# 1-Schematic_EMWAVER_DIY_V1.net
KiCad netlist of a schematic drawn in EasyEDA
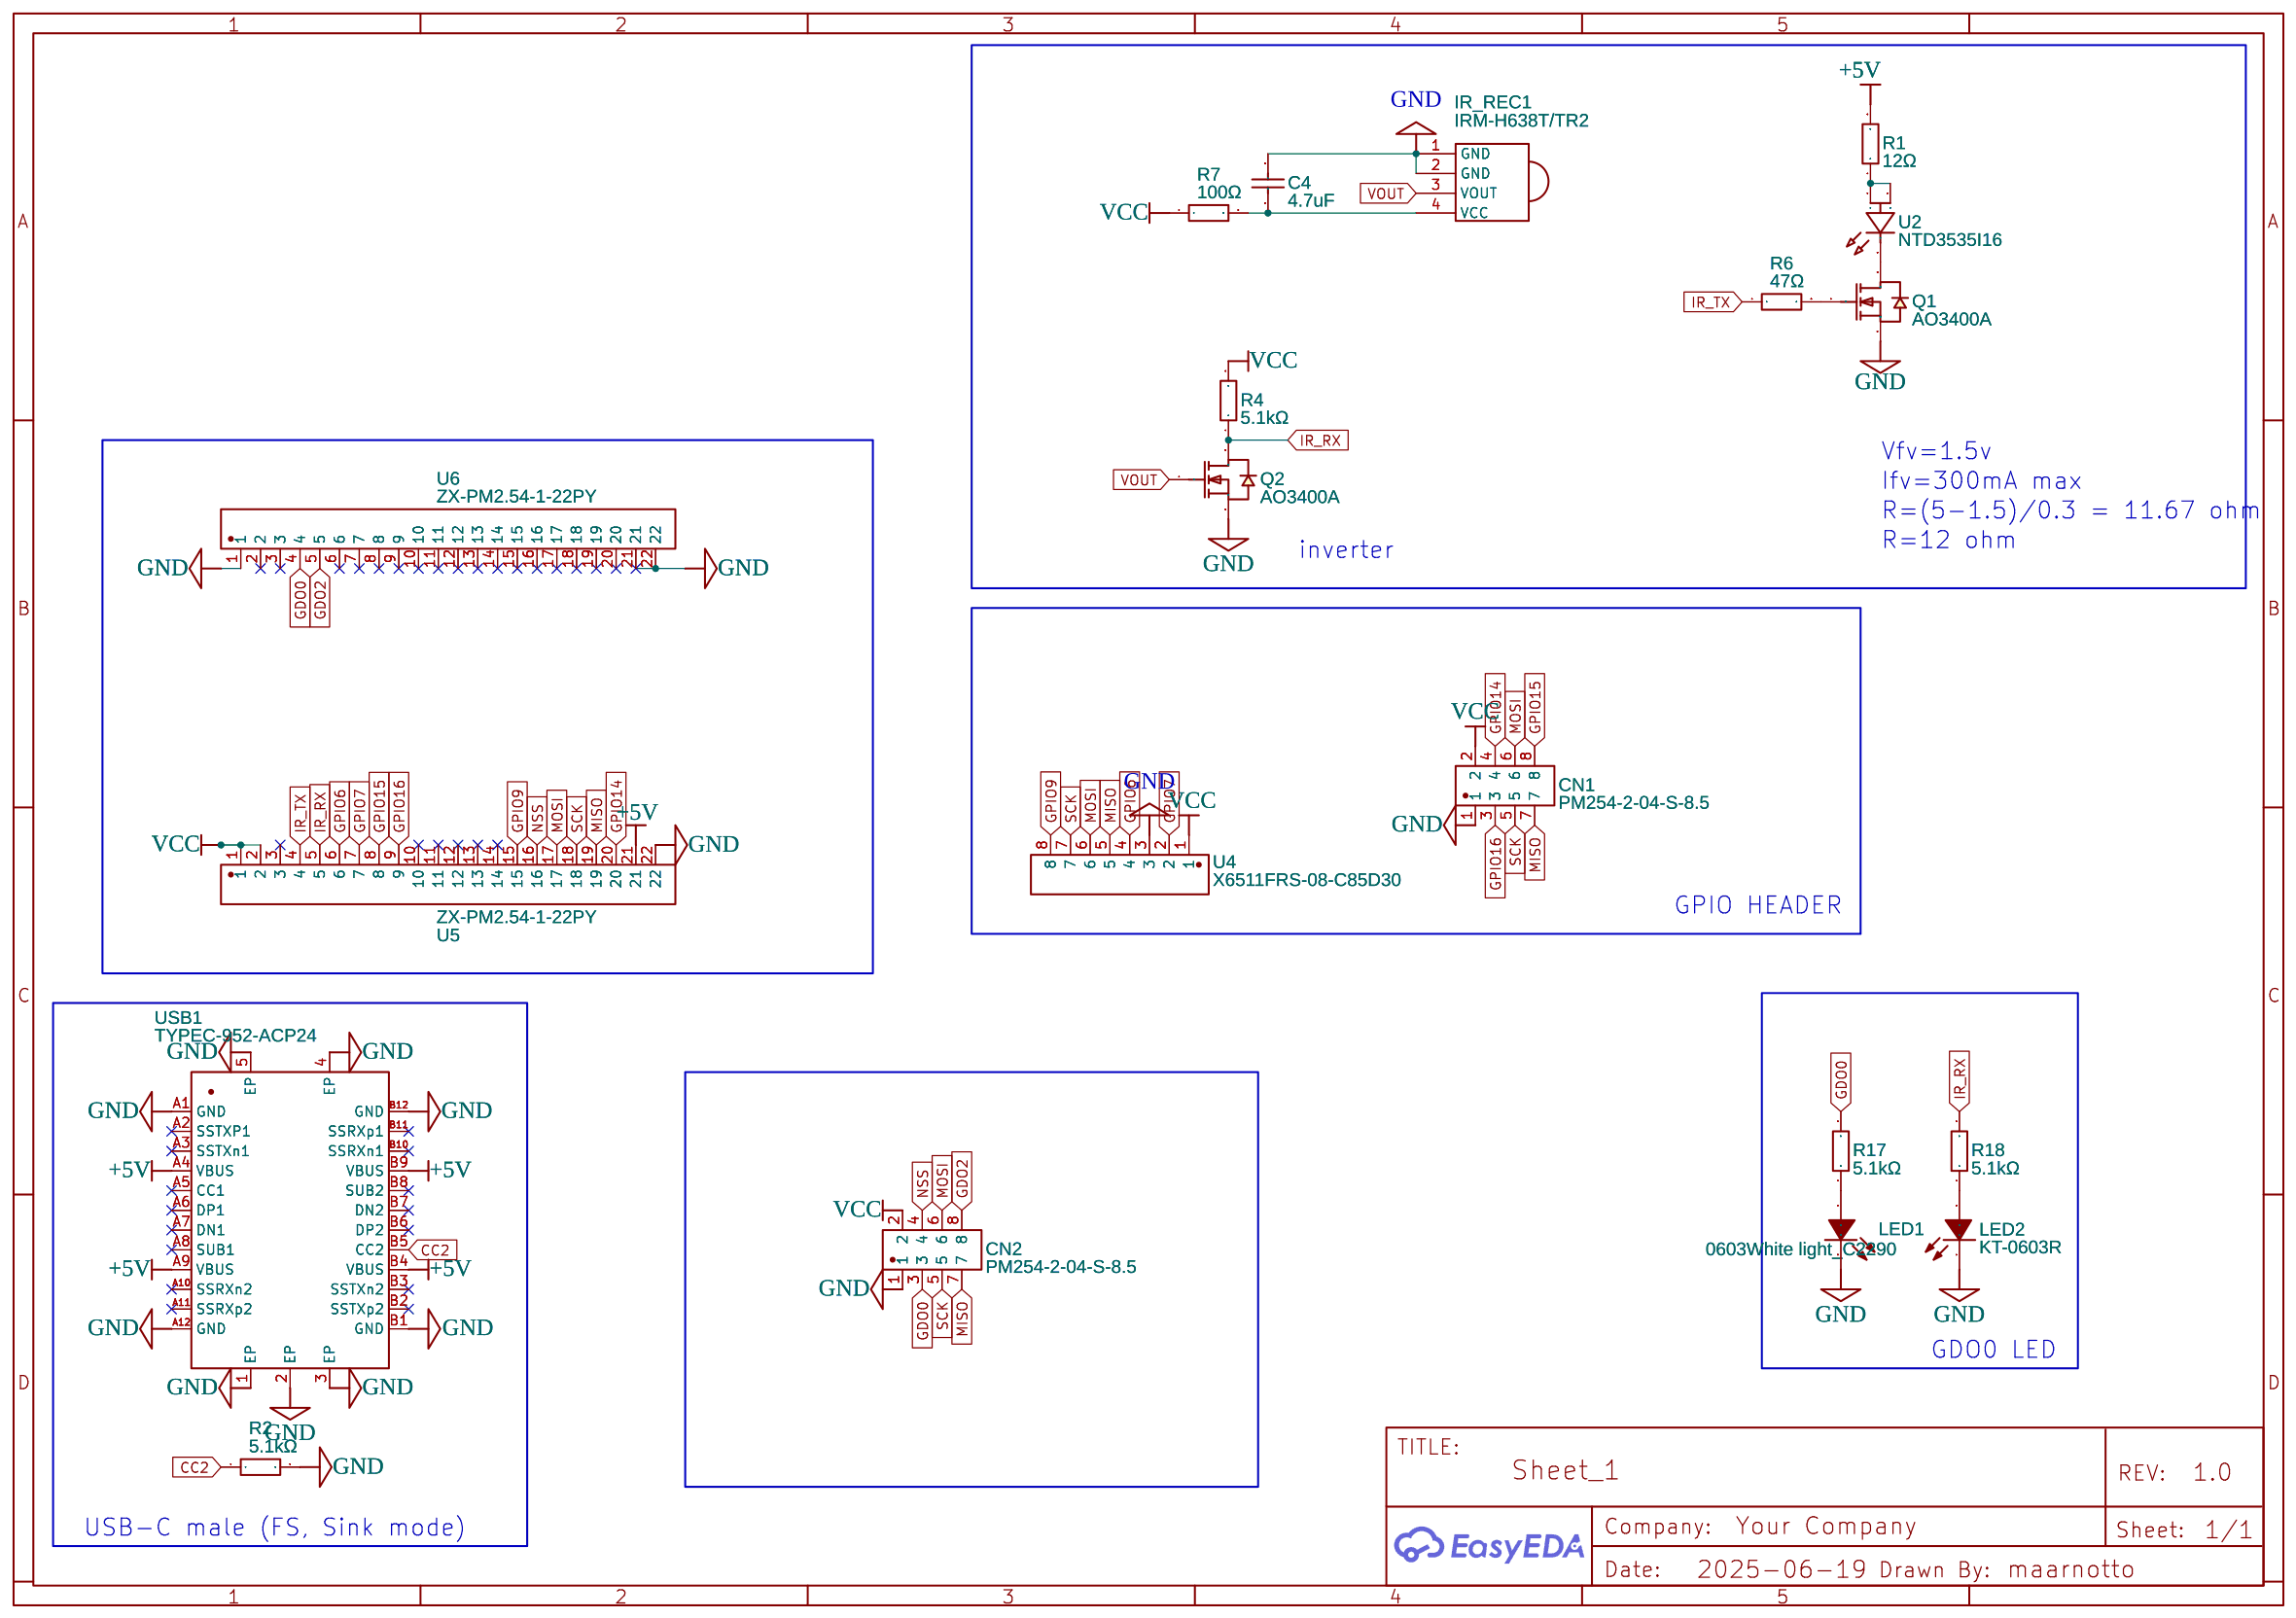
[diagram p0: schematic sheet]

(export (version "E")
  (design (tool "Eeschema 10.0.6"))
  (components
    (comp (ref "C4")
      (value "4.7uF")
      (fields
        (field (name "Manufacturer Part") "CL10A475KO8NNNC")
        (field (name "Manufacturer") "SAMSUNG(三星)")
      )
      (libsource (lib "") (part "CL10A475KO8NNNC"))
    )
    (comp (ref "CN1")
      (value "PM254-2-04-S-8.5")
      (fields (field (name "Manufacturer") "HCTL(华灿天禄)"))
      (libsource (lib "") (part "PM254-2-04-S-8.5"))
    )
    (comp (ref "CN2")
      (value "PM254-2-04-S-8.5")
      (fields (field (name "Manufacturer") "HCTL(华灿天禄)"))
      (libsource (lib "") (part "PM254-2-04-S-8.5"))
    )
    (comp (ref "IR_REC1")
      (value "IRM-H638T/TR2")
      (fields (field (name "Manufacturer") "EVERLIGHT(亿光)"))
      (libsource (lib "") (part "IRM-H638T/TR2"))
    )
    (comp (ref "LED1")
      (value "0603White light_C2290")
      (fields (field (name "Manufacturer Part") "KT-0603W") (field (name "Manufacturer") "KENTO"))
      (libsource (lib "") (part "0603White light_C2290"))
    )
    (comp (ref "LED2")
      (value "KT-0603R")
      (fields (field (name "Manufacturer") "KENTO"))
      (libsource (lib "") (part "KT-0603R"))
    )
    (comp (ref "Q1")
      (value "AO3400A")
      (fields (field (name "Manufacturer") "AOS"))
      (libsource (lib "") (part "AO3400A"))
    )
    (comp (ref "Q2")
      (value "AO3400A")
      (fields (field (name "Manufacturer") "AOS"))
      (libsource (lib "") (part "AO3400A"))
    )
    (comp (ref "R1")
      (value "12Ω")
      (fields
        (field (name "Manufacturer Part") "25121WJ0120T4E")
        (field (name "Manufacturer") "UNI-ROYAL(厚声)")
      )
      (libsource (lib "") (part "25121WJ0120T4E"))
    )
    (comp (ref "R2")
      (value "5.1kΩ")
      (fields
        (field (name "Manufacturer Part") "0603WAF5101T5E")
        (field (name "Manufacturer") "UNI-ROYAL(厚声)")
      )
      (libsource (lib "") (part "0603WAF5101T5E_1"))
    )
    (comp (ref "R4")
      (value "5.1kΩ")
      (fields
        (field (name "Manufacturer Part") "0603WAF5101T5E")
        (field (name "Manufacturer") "UNI-ROYAL(厚声)")
      )
      (libsource (lib "") (part "0603WAF5101T5E"))
    )
    (comp (ref "R6")
      (value "47Ω")
      (fields
        (field (name "Manufacturer Part") "0805W8F470JT5E")
        (field (name "Manufacturer") "UNI-ROYAL(厚声)")
      )
      (libsource (lib "") (part "0805W8F470JT5E"))
    )
    (comp (ref "R7")
      (value "100Ω")
      (fields
        (field (name "Manufacturer Part") "0805W8F1000T5E")
        (field (name "Manufacturer") "UNI-ROYAL(厚声)")
      )
      (libsource (lib "") (part "0805W8F1000T5E"))
    )
    (comp (ref "R17")
      (value "5.1kΩ")
      (fields
        (field (name "Manufacturer Part") "0603WAF5101T5E")
        (field (name "Manufacturer") "UNI-ROYAL(厚声)")
      )
      (libsource (lib "") (part "0603WAF5101T5E"))
    )
    (comp (ref "R18")
      (value "5.1kΩ")
      (fields
        (field (name "Manufacturer Part") "0603WAF5101T5E")
        (field (name "Manufacturer") "UNI-ROYAL(厚声)")
      )
      (libsource (lib "") (part "0603WAF5101T5E"))
    )
    (comp (ref "U2")
      (value "NTD3535I16")
      (fields (field (name "Manufacturer") "国星光电"))
      (libsource (lib "") (part "NTD3535I16"))
    )
    (comp (ref "U4")
      (value "X6511FRS-08-C85D30")
      (fields (field (name "Manufacturer") "XKB Connectivity(中国星坤)"))
      (libsource (lib "") (part "X6511FRS-08-C85D30"))
    )
    (comp (ref "U5")
      (value "ZX-PM2.54-1-22PY")
      (fields (field (name "Manufacturer") "Megastar(兆星)"))
      (libsource (lib "") (part "ZX-PM2.54-1-22PY_1"))
    )
    (comp (ref "U6")
      (value "ZX-PM2.54-1-22PY")
      (fields (field (name "Manufacturer") "Megastar(兆星)"))
      (libsource (lib "") (part "ZX-PM2.54-1-22PY"))
    )
    (comp (ref "USB1")
      (value "TYPEC-952-ACP24")
      (fields (field (name "Manufacturer") "XUNPU(讯普)"))
      (libsource (lib "") (part "TYPEC-952-ACP24"))
    )
  )
  (nets
    (net (code "1") (name "+5V") (class "Default")
      (node (ref "R1") (pin "2") (pinfunction "2_2") (pintype "input"))
      (node (ref "U5") (pin "21") (pinfunction "21_21") (pintype "unspecified"))
      (node (ref "USB1") (pin "A4") (pinfunction "VBUS_A4") (pintype "unspecified"))
      (node (ref "USB1") (pin "A9") (pinfunction "VBUS_A9") (pintype "unspecified"))
      (node (ref "USB1") (pin "B4") (pinfunction "VBUS_B4") (pintype "unspecified"))
      (node (ref "USB1") (pin "B9") (pinfunction "VBUS_B9") (pintype "unspecified"))
    )
    (net (code "2") (name "CC2") (class "Default")
      (node (ref "R2") (pin "1") (pinfunction "1_1") (pintype "input"))
      (node (ref "USB1") (pin "B5") (pinfunction "CC2_B5") (pintype "unspecified"))
    )
    (net (code "3") (name "GDO0") (class "Default")
      (node (ref "CN2") (pin "3") (pinfunction "3_3") (pintype "unspecified"))
      (node (ref "R17") (pin "2") (pinfunction "2_2") (pintype "input"))
      (node (ref "U6") (pin "4") (pinfunction "4_4") (pintype "unspecified"))
    )
    (net (code "4") (name "GDO2") (class "Default")
      (node (ref "CN2") (pin "8") (pinfunction "8_8") (pintype "unspecified"))
      (node (ref "U6") (pin "5") (pinfunction "5_5") (pintype "unspecified"))
    )
    (net (code "5") (name "GND") (class "Default")
      (node (ref "C4") (pin "2") (pinfunction "2_2") (pintype "input"))
      (node (ref "CN1") (pin "1") (pinfunction "1_1") (pintype "unspecified"))
      (node (ref "CN2") (pin "1") (pinfunction "1_1") (pintype "unspecified"))
      (node (ref "IR_REC1") (pin "1") (pinfunction "GND_1") (pintype "input"))
      (node (ref "IR_REC1") (pin "2") (pinfunction "GND_2") (pintype "input"))
      (node (ref "LED1") (pin "2") (pinfunction "K_2") (pintype "unspecified"))
      (node (ref "LED2") (pin "1") (pinfunction "K_1") (pintype "unspecified"))
      (node (ref "Q1") (pin "2") (pinfunction "S_2") (pintype "unspecified"))
      (node (ref "Q2") (pin "2") (pinfunction "S_2") (pintype "unspecified"))
      (node (ref "R2") (pin "2") (pinfunction "2_2") (pintype "input"))
      (node (ref "U4") (pin "3") (pinfunction "3_3") (pintype "unspecified"))
      (node (ref "U5") (pin "22") (pinfunction "22_22") (pintype "unspecified"))
      (node (ref "U6") (pin "1") (pinfunction "1_1") (pintype "unspecified"))
      (node (ref "U6") (pin "21") (pinfunction "21_21") (pintype "unspecified"))
      (node (ref "U6") (pin "22") (pinfunction "22_22") (pintype "unspecified"))
      (node (ref "USB1") (pin "1") (pinfunction "EP_1") (pintype "unspecified"))
      (node (ref "USB1") (pin "2") (pinfunction "EP_2") (pintype "unspecified"))
      (node (ref "USB1") (pin "3") (pinfunction "EP_3") (pintype "unspecified"))
      (node (ref "USB1") (pin "4") (pinfunction "EP_4") (pintype "unspecified"))
      (node (ref "USB1") (pin "5") (pinfunction "EP_5") (pintype "unspecified"))
      (node (ref "USB1") (pin "A1") (pinfunction "GND_A1") (pintype "unspecified"))
      (node (ref "USB1") (pin "A12") (pinfunction "GND_A12") (pintype "unspecified"))
      (node (ref "USB1") (pin "B1") (pinfunction "GND_B1") (pintype "unspecified"))
      (node (ref "USB1") (pin "B12") (pinfunction "GND_B12") (pintype "unspecified"))
    )
    (net (code "6") (name "GPIO6") (class "Default")
      (node (ref "U4") (pin "4") (pinfunction "4_4") (pintype "unspecified"))
      (node (ref "U5") (pin "6") (pinfunction "6_6") (pintype "unspecified"))
    )
    (net (code "7") (name "GPIO7") (class "Default")
      (node (ref "U4") (pin "2") (pinfunction "2_2") (pintype "unspecified"))
      (node (ref "U5") (pin "7") (pinfunction "7_7") (pintype "unspecified"))
    )
    (net (code "8") (name "GPIO9") (class "Default")
      (node (ref "U4") (pin "8") (pinfunction "8_8") (pintype "unspecified"))
      (node (ref "U5") (pin "15") (pinfunction "15_15") (pintype "unspecified"))
    )
    (net (code "9") (name "GPIO14") (class "Default")
      (node (ref "CN1") (pin "4") (pinfunction "4_4") (pintype "unspecified"))
      (node (ref "U5") (pin "20") (pinfunction "20_20") (pintype "unspecified"))
    )
    (net (code "10") (name "GPIO15") (class "Default")
      (node (ref "CN1") (pin "8") (pinfunction "8_8") (pintype "unspecified"))
      (node (ref "U5") (pin "8") (pinfunction "8_8") (pintype "unspecified"))
    )
    (net (code "11") (name "GPIO16") (class "Default")
      (node (ref "CN1") (pin "3") (pinfunction "3_3") (pintype "unspecified"))
      (node (ref "U5") (pin "9") (pinfunction "9_9") (pintype "unspecified"))
    )
    (net (code "12") (name "IR_RX") (class "Default")
      (node (ref "Q2") (pin "3") (pinfunction "D_3") (pintype "unspecified"))
      (node (ref "R18") (pin "2") (pinfunction "2_2") (pintype "input"))
      (node (ref "R4") (pin "1") (pinfunction "1_1") (pintype "input"))
      (node (ref "U5") (pin "5") (pinfunction "5_5") (pintype "unspecified"))
    )
    (net (code "13") (name "IR_TX") (class "Default")
      (node (ref "R6") (pin "1") (pinfunction "1_1") (pintype "input"))
      (node (ref "U5") (pin "4") (pinfunction "4_4") (pintype "unspecified"))
    )
    (net (code "14") (name "MISO") (class "Default")
      (node (ref "CN1") (pin "7") (pinfunction "7_7") (pintype "unspecified"))
      (node (ref "CN2") (pin "7") (pinfunction "7_7") (pintype "unspecified"))
      (node (ref "U4") (pin "5") (pinfunction "5_5") (pintype "unspecified"))
      (node (ref "U5") (pin "19") (pinfunction "19_19") (pintype "unspecified"))
    )
    (net (code "15") (name "MOSI") (class "Default")
      (node (ref "CN1") (pin "6") (pinfunction "6_6") (pintype "unspecified"))
      (node (ref "CN2") (pin "6") (pinfunction "6_6") (pintype "unspecified"))
      (node (ref "U4") (pin "6") (pinfunction "6_6") (pintype "unspecified"))
      (node (ref "U5") (pin "17") (pinfunction "17_17") (pintype "unspecified"))
    )
    (net (code "16") (name "NSS") (class "Default")
      (node (ref "CN2") (pin "4") (pinfunction "4_4") (pintype "unspecified"))
      (node (ref "U5") (pin "16") (pinfunction "16_16") (pintype "unspecified"))
    )
    (net (code "17") (name "Net-(IR_REC1-VCC)") (class "Default")
      (node (ref "C4") (pin "1") (pinfunction "1_1") (pintype "input"))
      (node (ref "IR_REC1") (pin "4") (pinfunction "VCC_4") (pintype "input"))
      (node (ref "R7") (pin "2") (pinfunction "2_2") (pintype "input"))
    )
    (net (code "18") (name "Net-(LED1-A)") (class "Default")
      (node (ref "LED1") (pin "1") (pinfunction "A_1") (pintype "unspecified"))
      (node (ref "R17") (pin "1") (pinfunction "1_1") (pintype "input"))
    )
    (net (code "19") (name "Net-(LED2-A)") (class "Default")
      (node (ref "LED2") (pin "2") (pinfunction "A_2") (pintype "unspecified"))
      (node (ref "R18") (pin "1") (pinfunction "1_1") (pintype "input"))
    )
    (net (code "20") (name "Net-(Q1-D)") (class "Default")
      (node (ref "Q1") (pin "3") (pinfunction "D_3") (pintype "unspecified"))
      (node (ref "U2") (pin "3") (pinfunction "K_3") (pintype "unspecified"))
    )
    (net (code "21") (name "Net-(Q1-G)") (class "Default")
      (node (ref "Q1") (pin "1") (pinfunction "G_1") (pintype "unspecified"))
      (node (ref "R6") (pin "2") (pinfunction "2_2") (pintype "input"))
    )
    (net (code "22") (name "Net-(U2-A)") (class "Default")
      (node (ref "R1") (pin "1") (pinfunction "1_1") (pintype "input"))
      (node (ref "U2") (pin "1") (pinfunction "A_1") (pintype "unspecified"))
      (node (ref "U2") (pin "2") (pinfunction "2_2") (pintype "unspecified"))
    )
    (net (code "23") (name "SCK") (class "Default")
      (node (ref "CN1") (pin "5") (pinfunction "5_5") (pintype "unspecified"))
      (node (ref "CN2") (pin "5") (pinfunction "5_5") (pintype "unspecified"))
      (node (ref "U4") (pin "7") (pinfunction "7_7") (pintype "unspecified"))
      (node (ref "U5") (pin "18") (pinfunction "18_18") (pintype "unspecified"))
    )
    (net (code "24") (name "VCC") (class "Default")
      (node (ref "CN1") (pin "2") (pinfunction "2_2") (pintype "unspecified"))
      (node (ref "CN2") (pin "2") (pinfunction "2_2") (pintype "unspecified"))
      (node (ref "R4") (pin "2") (pinfunction "2_2") (pintype "input"))
      (node (ref "R7") (pin "1") (pinfunction "1_1") (pintype "input"))
      (node (ref "U4") (pin "1") (pinfunction "1_1") (pintype "unspecified"))
      (node (ref "U5") (pin "1") (pinfunction "1_1") (pintype "unspecified"))
      (node (ref "U5") (pin "2") (pinfunction "2_2") (pintype "unspecified"))
    )
    (net (code "25") (name "VOUT") (class "Default")
      (node (ref "IR_REC1") (pin "3") (pinfunction "VOUT_3") (pintype "input"))
      (node (ref "Q2") (pin "1") (pinfunction "G_1") (pintype "unspecified"))
    )
    (net (code "26") (name "unconnected-(U5-Pad3)") (class "Default")
      (node (ref "U5") (pin "3") (pinfunction "3_3") (pintype "unspecified+no_connect"))
    )
    (net (code "27") (name "unconnected-(U5-Pad10)") (class "Default")
      (node (ref "U5") (pin "10") (pinfunction "10_10") (pintype "unspecified+no_connect"))
    )
    (net (code "28") (name "unconnected-(U5-Pad11)") (class "Default")
      (node (ref "U5") (pin "11") (pinfunction "11_11") (pintype "unspecified+no_connect"))
    )
    (net (code "29") (name "unconnected-(U5-Pad12)") (class "Default")
      (node (ref "U5") (pin "12") (pinfunction "12_12") (pintype "unspecified+no_connect"))
    )
    (net (code "30") (name "unconnected-(U5-Pad13)") (class "Default")
      (node (ref "U5") (pin "13") (pinfunction "13_13") (pintype "unspecified+no_connect"))
    )
    (net (code "31") (name "unconnected-(U5-Pad14)") (class "Default")
      (node (ref "U5") (pin "14") (pinfunction "14_14") (pintype "unspecified+no_connect"))
    )
    (net (code "32") (name "unconnected-(U6-Pad2)") (class "Default")
      (node (ref "U6") (pin "2") (pinfunction "2_2") (pintype "unspecified+no_connect"))
    )
    (net (code "33") (name "unconnected-(U6-Pad3)") (class "Default")
      (node (ref "U6") (pin "3") (pinfunction "3_3") (pintype "unspecified+no_connect"))
    )
    (net (code "34") (name "unconnected-(U6-Pad6)") (class "Default")
      (node (ref "U6") (pin "6") (pinfunction "6_6") (pintype "unspecified+no_connect"))
    )
    (net (code "35") (name "unconnected-(U6-Pad7)") (class "Default")
      (node (ref "U6") (pin "7") (pinfunction "7_7") (pintype "unspecified+no_connect"))
    )
    (net (code "36") (name "unconnected-(U6-Pad8)") (class "Default")
      (node (ref "U6") (pin "8") (pinfunction "8_8") (pintype "unspecified+no_connect"))
    )
    (net (code "37") (name "unconnected-(U6-Pad9)") (class "Default")
      (node (ref "U6") (pin "9") (pinfunction "9_9") (pintype "unspecified+no_connect"))
    )
    (net (code "38") (name "unconnected-(U6-Pad10)") (class "Default")
      (node (ref "U6") (pin "10") (pinfunction "10_10") (pintype "unspecified+no_connect"))
    )
    (net (code "39") (name "unconnected-(U6-Pad11)") (class "Default")
      (node (ref "U6") (pin "11") (pinfunction "11_11") (pintype "unspecified+no_connect"))
    )
    (net (code "40") (name "unconnected-(U6-Pad12)") (class "Default")
      (node (ref "U6") (pin "12") (pinfunction "12_12") (pintype "unspecified+no_connect"))
    )
    (net (code "41") (name "unconnected-(U6-Pad13)") (class "Default")
      (node (ref "U6") (pin "13") (pinfunction "13_13") (pintype "unspecified+no_connect"))
    )
    (net (code "42") (name "unconnected-(U6-Pad14)") (class "Default")
      (node (ref "U6") (pin "14") (pinfunction "14_14") (pintype "unspecified+no_connect"))
    )
    (net (code "43") (name "unconnected-(U6-Pad15)") (class "Default")
      (node (ref "U6") (pin "15") (pinfunction "15_15") (pintype "unspecified+no_connect"))
    )
    (net (code "44") (name "unconnected-(U6-Pad16)") (class "Default")
      (node (ref "U6") (pin "16") (pinfunction "16_16") (pintype "unspecified+no_connect"))
    )
    (net (code "45") (name "unconnected-(U6-Pad17)") (class "Default")
      (node (ref "U6") (pin "17") (pinfunction "17_17") (pintype "unspecified+no_connect"))
    )
    (net (code "46") (name "unconnected-(U6-Pad18)") (class "Default")
      (node (ref "U6") (pin "18") (pinfunction "18_18") (pintype "unspecified+no_connect"))
    )
    (net (code "47") (name "unconnected-(U6-Pad19)") (class "Default")
      (node (ref "U6") (pin "19") (pinfunction "19_19") (pintype "unspecified+no_connect"))
    )
    (net (code "48") (name "unconnected-(U6-Pad20)") (class "Default")
      (node (ref "U6") (pin "20") (pinfunction "20_20") (pintype "unspecified+no_connect"))
    )
    (net (code "49") (name "unconnected-(USB1-CC1-PadA5)") (class "Default")
      (node (ref "USB1") (pin "A5") (pinfunction "CC1_A5") (pintype "unspecified+no_connect"))
    )
    (net (code "50") (name "unconnected-(USB1-DN1-PadA7)") (class "Default")
      (node (ref "USB1") (pin "A7") (pinfunction "DN1_A7") (pintype "unspecified+no_connect"))
    )
    (net (code "51") (name "unconnected-(USB1-DN2-PadB7)") (class "Default")
      (node (ref "USB1") (pin "B7") (pinfunction "DN2_B7") (pintype "unspecified+no_connect"))
    )
    (net (code "52") (name "unconnected-(USB1-DP1-PadA6)") (class "Default")
      (node (ref "USB1") (pin "A6") (pinfunction "DP1_A6") (pintype "unspecified+no_connect"))
    )
    (net (code "53") (name "unconnected-(USB1-DP2-PadB6)") (class "Default")
      (node (ref "USB1") (pin "B6") (pinfunction "DP2_B6") (pintype "unspecified+no_connect"))
    )
    (net (code "54") (name "unconnected-(USB1-SSRXn1-PadB10)") (class "Default")
      (node (ref "USB1") (pin "B10") (pinfunction "SSRXn1_B10") (pintype "unspecified+no_connect"))
    )
    (net (code "55") (name "unconnected-(USB1-SSRXn2-PadA10)") (class "Default")
      (node (ref "USB1") (pin "A10") (pinfunction "SSRXn2_A10") (pintype "unspecified+no_connect"))
    )
    (net (code "56") (name "unconnected-(USB1-SSRXp1-PadB11)") (class "Default")
      (node (ref "USB1") (pin "B11") (pinfunction "SSRXp1_B11") (pintype "unspecified+no_connect"))
    )
    (net (code "57") (name "unconnected-(USB1-SSRXp2-PadA11)") (class "Default")
      (node (ref "USB1") (pin "A11") (pinfunction "SSRXp2_A11") (pintype "unspecified+no_connect"))
    )
    (net (code "58") (name "unconnected-(USB1-SSTXP1-PadA2)") (class "Default")
      (node (ref "USB1") (pin "A2") (pinfunction "SSTXP1_A2") (pintype "unspecified+no_connect"))
    )
    (net (code "59") (name "unconnected-(USB1-SSTXn1-PadA3)") (class "Default")
      (node (ref "USB1") (pin "A3") (pinfunction "SSTXn1_A3") (pintype "unspecified+no_connect"))
    )
    (net (code "60") (name "unconnected-(USB1-SSTXn2-PadB3)") (class "Default")
      (node (ref "USB1") (pin "B3") (pinfunction "SSTXn2_B3") (pintype "unspecified+no_connect"))
    )
    (net (code "61") (name "unconnected-(USB1-SSTXp2-PadB2)") (class "Default")
      (node (ref "USB1") (pin "B2") (pinfunction "SSTXp2_B2") (pintype "unspecified+no_connect"))
    )
    (net (code "62") (name "unconnected-(USB1-SUB1-PadA8)") (class "Default")
      (node (ref "USB1") (pin "A8") (pinfunction "SUB1_A8") (pintype "unspecified+no_connect"))
    )
    (net (code "63") (name "unconnected-(USB1-SUB2-PadB8)") (class "Default")
      (node (ref "USB1") (pin "B8") (pinfunction "SUB2_B8") (pintype "unspecified+no_connect"))
    )
  )
)
